# 42mm_Erweiterungsplatine.net
KiCad netlist of a schematic drawn in EAGLE
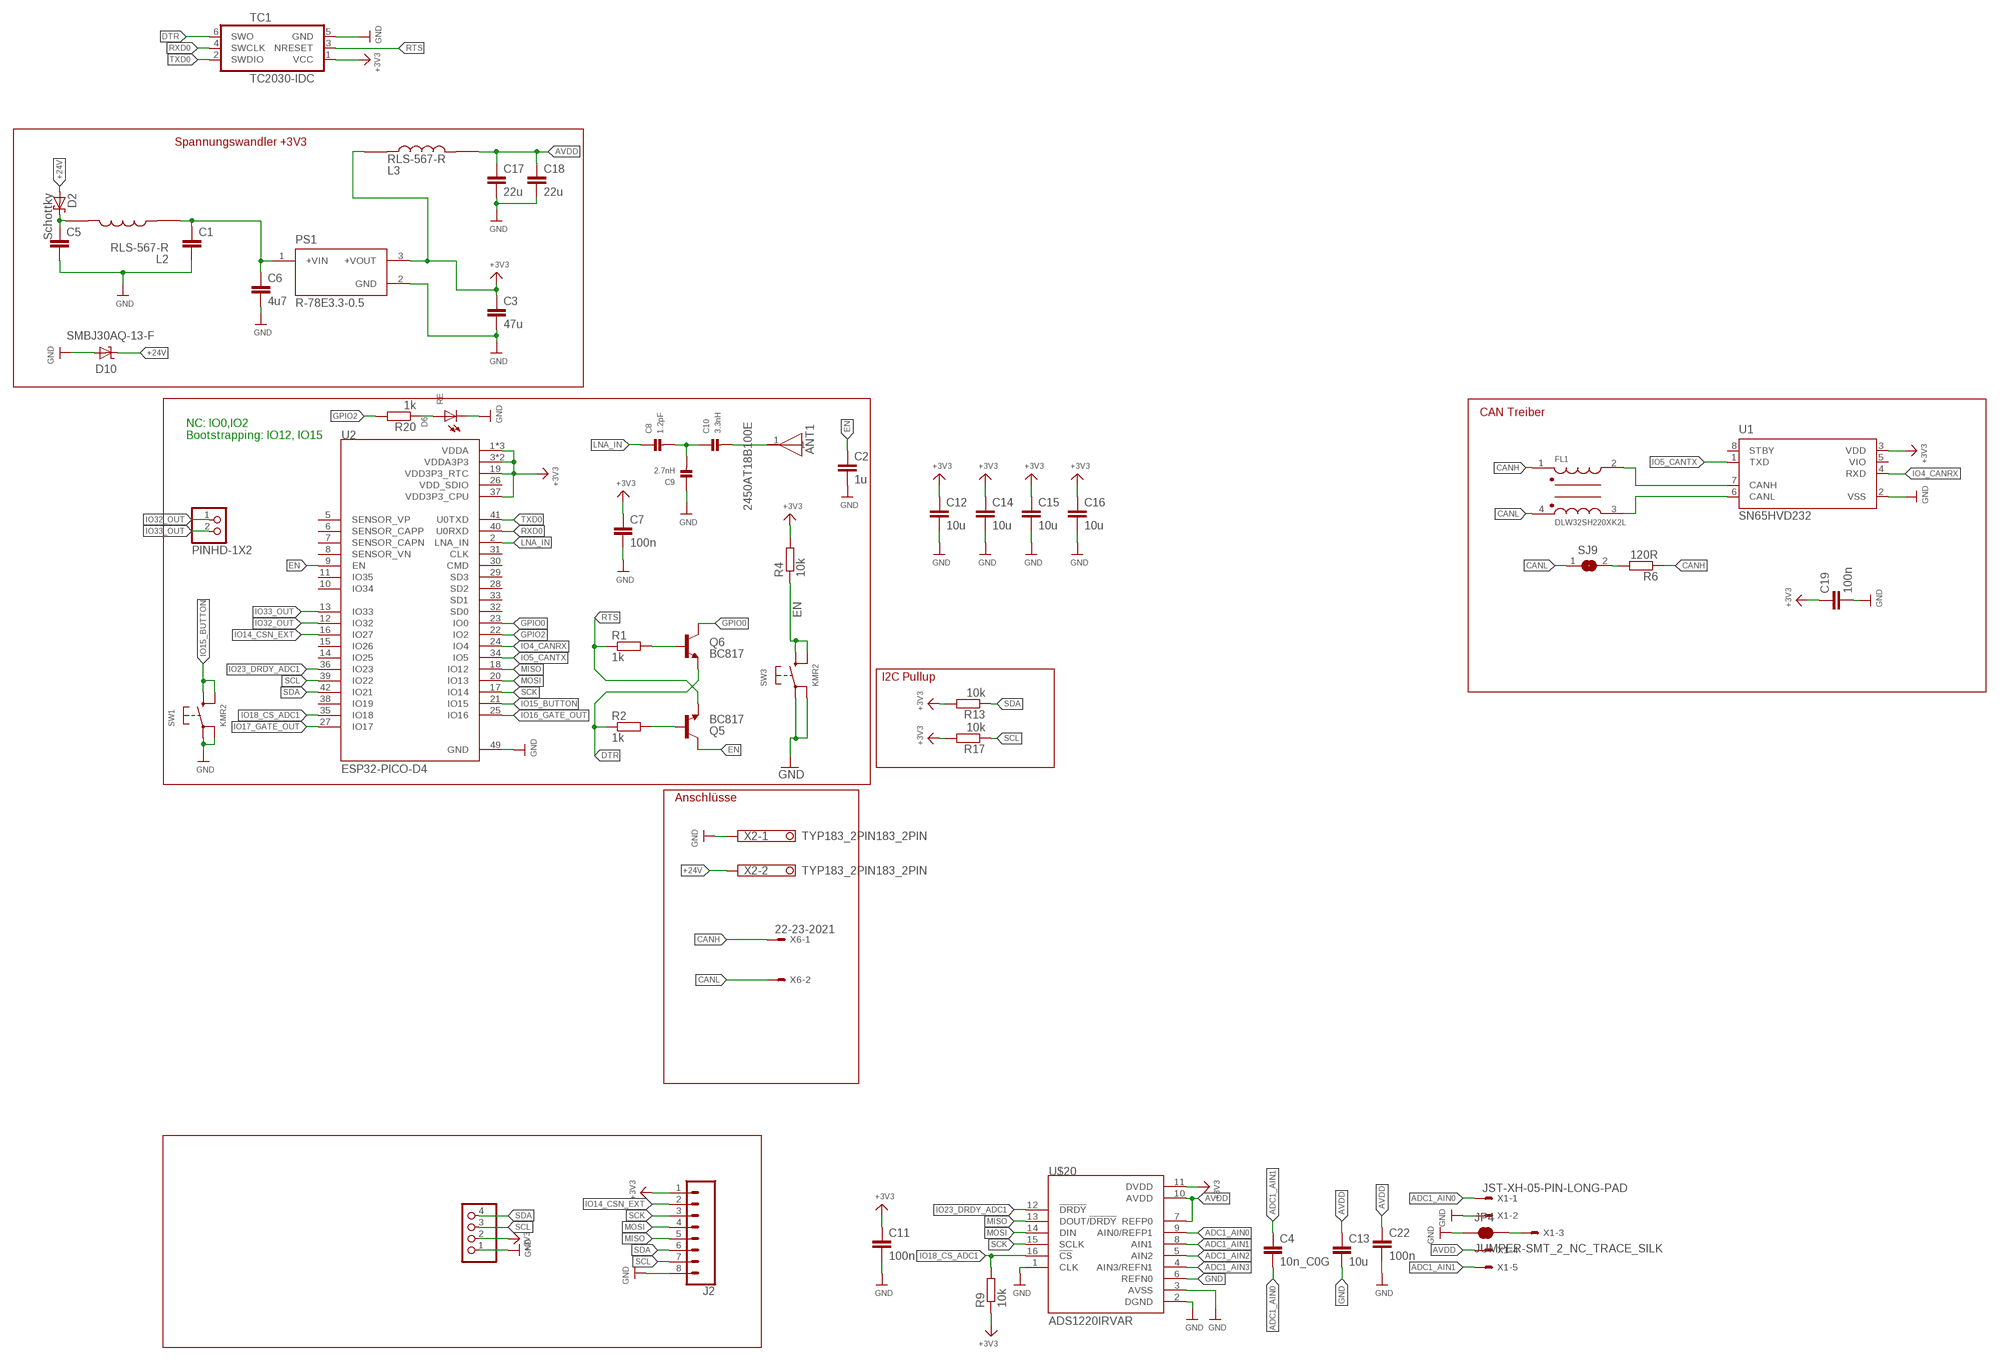
[diagram p0: schematic, sheet 1]

(export (version "E")
  (design (tool "Eeschema 10.0.6"))
  (components
    (comp (ref "ANT1")
      (value "2450AT18B100E")
      (footprint "eagle-import:ANT_2450AT18B100E")
      (fields (field (name "MF") "Johanson Technology"))
      (libsource (lib "eagle-import") (part "2450AT18B100E"))
    )
    (comp (ref "C1")
      (value "C-EUC1206K")
      (footprint "eagle-import:C1206K")
      (libsource (lib "eagle-import") (part "C-EUC1206K"))
    )
    (comp (ref "C2")
      (value "1u")
      (footprint "eagle-import:C0805")
      (libsource (lib "eagle-import") (part "C-EUC0805"))
    )
    (comp (ref "C3")
      (value "47u")
      (footprint "eagle-import:C0805")
      (libsource (lib "eagle-import") (part "C-EUC0805"))
    )
    (comp (ref "C4")
      (value "10n_C0G")
      (footprint "eagle-import:C0805")
      (libsource (lib "eagle-import") (part "C-EUC0805"))
    )
    (comp (ref "C5")
      (value "C-EUC1206K")
      (footprint "eagle-import:C1206K")
      (libsource (lib "eagle-import") (part "C-EUC1206K"))
    )
    (comp (ref "C6")
      (value "4u7")
      (footprint "eagle-import:C0805")
      (libsource (lib "eagle-import") (part "C-EUC0805"))
    )
    (comp (ref "C7")
      (value "100n")
      (footprint "eagle-import:C0805")
      (libsource (lib "eagle-import") (part "C-EUC0805"))
    )
    (comp (ref "C8")
      (value "1.2pF")
      (footprint "eagle-import:_0402MP")
      (libsource (lib "eagle-import") (part "CAP_CERAMIC_0402MP"))
    )
    (comp (ref "C9")
      (value "2.7nH")
      (footprint "eagle-import:_0402MP")
      (libsource (lib "eagle-import") (part "CAP_CERAMIC_0402MP"))
    )
    (comp (ref "C10")
      (value "3.3nH")
      (footprint "eagle-import:_0402MP")
      (libsource (lib "eagle-import") (part "CAP_CERAMIC_0402MP"))
    )
    (comp (ref "C11")
      (value "100n")
      (footprint "eagle-import:C0805")
      (libsource (lib "eagle-import") (part "C-EUC0805"))
    )
    (comp (ref "C12")
      (value "10u")
      (footprint "eagle-import:C0805")
      (libsource (lib "eagle-import") (part "C-EUC0805"))
    )
    (comp (ref "C13")
      (value "10u")
      (footprint "eagle-import:C0805")
      (libsource (lib "eagle-import") (part "C-EUC0805"))
    )
    (comp (ref "C14")
      (value "10u")
      (footprint "eagle-import:C0805")
      (libsource (lib "eagle-import") (part "C-EUC0805"))
    )
    (comp (ref "C15")
      (value "10u")
      (footprint "eagle-import:C0805")
      (libsource (lib "eagle-import") (part "C-EUC0805"))
    )
    (comp (ref "C16")
      (value "10u")
      (footprint "eagle-import:C0805")
      (libsource (lib "eagle-import") (part "C-EUC0805"))
    )
    (comp (ref "C17")
      (value "22u")
      (footprint "eagle-import:C0805")
      (libsource (lib "eagle-import") (part "C-EUC0805"))
    )
    (comp (ref "C18")
      (value "22u")
      (footprint "eagle-import:C0805")
      (libsource (lib "eagle-import") (part "C-EUC0805"))
    )
    (comp (ref "C19")
      (value "100n")
      (footprint "eagle-import:C0805")
      (libsource (lib "eagle-import") (part "C-EUC0805"))
    )
    (comp (ref "C22")
      (value "100n")
      (footprint "eagle-import:C0805")
      (libsource (lib "eagle-import") (part "C-EUC0805"))
    )
    (comp (ref "D2")
      (value "Schottky")
      (footprint "eagle-import:SMB")
      (libsource (lib "eagle-import") (part "SCHOTTKY-DIODESMD"))
    )
    (comp (ref "D6")
      (value "RE")
      (footprint "eagle-import:CHIP-LED0805")
      (libsource (lib "eagle-import") (part "LEDCHIP-LED0805"))
    )
    (comp (ref "D10")
      (value "SMBJ30AQ-13-F")
      (footprint "eagle-import:SMBJ")
      (libsource (lib "eagle-import") (part "SUPPRESSOR-SMBJ"))
    )
    (comp (ref "FL1")
      (value "DLW32SH220XK2L")
      (footprint "eagle-import:FIL_DLW32SH110XK2L")
      (fields (field (name "MF") "Murata") (field (name "MP") "DLW32SH110XK2L"))
      (libsource (lib "eagle-import") (part "DLW32SH110XK2L"))
    )
    (comp (ref "J2")
      (value "CONN_08BM08B-SRSS-TB")
      (footprint "eagle-import:BM08B-SRSS-TB")
      (libsource (lib "eagle-import") (part "CONN_08BM08B-SRSS-TB"))
    )
    (comp (ref "JP1")
      (value "PINHD-1X4")
      (footprint "eagle-import:1X04")
      (libsource (lib "eagle-import") (part "PINHD-1X4"))
    )
    (comp (ref "JP4")
      (value "JUMPER-SMT_2_NC_TRACE_SILK")
      (footprint "eagle-import:SMT-JUMPER_2_NC_TRACE_SILK")
      (libsource (lib "eagle-import") (part "JUMPER-SMT_2_NC_TRACE_SILK"))
    )
    (comp (ref "JP5")
      (value "PINHD-1X2")
      (footprint "eagle-import:1X02")
      (libsource (lib "eagle-import") (part "PINHD-1X2"))
    )
    (comp (ref "L2")
      (value "RLS-567-R")
      (footprint "eagle-import:IND_RLS-567-R")
      (fields (field (name "MF") "Recom Power"))
      (libsource (lib "eagle-import") (part "RLS-567-R"))
    )
    (comp (ref "L3")
      (value "RLS-567-R")
      (footprint "eagle-import:IND_RLS-567-R")
      (fields (field (name "MF") "Recom Power"))
      (libsource (lib "eagle-import") (part "RLS-567-R"))
    )
    (comp (ref "PS1")
      (value "R-78E3.3-0.5")
      (footprint "eagle-import:CONV_R-78E3.3-0.5")
      (fields (field (name "MF") "Recom Power"))
      (libsource (lib "eagle-import") (part "R-78E3.3-0.5"))
    )
    (comp (ref "Q5")
      (value "BC817")
      (footprint "eagle-import:SOT23-3")
      (libsource (lib "eagle-import") (part "TRANSISTOR_NPNSOT23-3"))
    )
    (comp (ref "Q6")
      (value "BC817")
      (footprint "eagle-import:SOT23-3")
      (libsource (lib "eagle-import") (part "TRANSISTOR_NPNSOT23-3"))
    )
    (comp (ref "R1")
      (value "1k")
      (footprint "eagle-import:R0805")
      (libsource (lib "eagle-import") (part "R-EU_R0805"))
    )
    (comp (ref "R2")
      (value "1k")
      (footprint "eagle-import:R0805")
      (libsource (lib "eagle-import") (part "R-EU_R0805"))
    )
    (comp (ref "R4")
      (value "10k")
      (footprint "eagle-import:R0805")
      (libsource (lib "eagle-import") (part "R-EU_R0805"))
    )
    (comp (ref "R6")
      (value "120R")
      (footprint "eagle-import:R0805")
      (libsource (lib "eagle-import") (part "R-EU_R0805"))
    )
    (comp (ref "R9")
      (value "10k")
      (footprint "eagle-import:R0805")
      (libsource (lib "eagle-import") (part "R-EU_R0805"))
    )
    (comp (ref "R13")
      (value "10k")
      (footprint "eagle-import:R0805")
      (libsource (lib "eagle-import") (part "R-EU_R0805"))
    )
    (comp (ref "R17")
      (value "10k")
      (footprint "eagle-import:R0805")
      (libsource (lib "eagle-import") (part "R-EU_R0805"))
    )
    (comp (ref "R20")
      (value "1k")
      (footprint "eagle-import:R0805")
      (libsource (lib "eagle-import") (part "R-EU_R0805"))
    )
    (comp (ref "SJ9") (value "SJ") (footprint "eagle-import:SJ") (libsource (lib "eagle-import") (part "SJ")))
    (comp (ref "SW1")
      (value "KMR2")
      (footprint "eagle-import:BTN_KMR2_4.6X2.8")
      (libsource (lib "eagle-import") (part "SWITCH_TACT_SMT4.6X2.8"))
    )
    (comp (ref "SW3")
      (value "KMR2")
      (footprint "eagle-import:BTN_KMR2_4.6X2.8")
      (libsource (lib "eagle-import") (part "SWITCH_TACT_SMT4.6X2.8"))
    )
    (comp (ref "TC1")
      (value "TC2030-IDC")
      (footprint "eagle-import:TC2030-IDC")
      (fields (field (name "MF") "Tag-Connect LLC"))
      (libsource (lib "eagle-import") (part "TC2030-IDC"))
    )
    (comp (ref "U$20")
      (value "ADS1220IRVAR")
      (footprint "eagle-import:QFN50P350X350X100-17N214X214")
      (libsource (lib "eagle-import") (part "ADS1220IRVAR"))
    )
    (comp (ref "U1")
      (value "SN65HVD232")
      (footprint "eagle-import:SOIC127P600X175-8N")
      (fields (field (name "MF") "Microchip") (field (name "MP") "MCP2562-E/SN"))
      (libsource (lib "eagle-import") (part "MCP2562-E/SN"))
    )
    (comp (ref "U2")
      (value "ESP32-PICO-D4")
      (footprint "eagle-import:PQFN50P700X700X104-49N")
      (fields (field (name "MF") "Espressif Systems"))
      (libsource (lib "eagle-import") (part "ESP32-PICO-D4"))
    )
    (comp (ref "X1")
      (value "JST-XH-05-PIN-LONG-PAD")
      (footprint "eagle-import:JST-XH-05-PACKAGE-LONG-PAD")
      (libsource (lib "eagle-import") (part "JST-XH-05-PIN-LONG-PAD"))
    )
    (comp (ref "X2")
      (value "TYP183_2PIN183_2PIN")
      (footprint "eagle-import:TYP183_FT_2PIN")
      (libsource (lib "eagle-import") (part "TYP183_2PIN183_2PIN"))
    )
    (comp (ref "X6")
      (value "22-23-2021")
      (footprint "eagle-import:22-23-2021")
      (fields (field (name "MF") "MOLEX"))
      (libsource (lib "eagle-import") (part "22-23-2021"))
    )
  )
  (nets
    (net (code "1") (name "+3V3") (class "Default")
      (node (ref "C11") (pin "1") (pinfunction "1_1") (pintype "passive"))
      (node (ref "C12") (pin "1") (pinfunction "1_1") (pintype "passive"))
      (node (ref "C14") (pin "1") (pinfunction "1_1") (pintype "passive"))
      (node (ref "C15") (pin "1") (pinfunction "1_1") (pintype "passive"))
      (node (ref "C16") (pin "1") (pinfunction "1_1") (pintype "passive"))
      (node (ref "C19") (pin "1") (pinfunction "1_1") (pintype "passive"))
      (node (ref "C3") (pin "1") (pinfunction "1_1") (pintype "passive"))
      (node (ref "C7") (pin "1") (pinfunction "1_1") (pintype "passive"))
      (node (ref "J2") (pin "1") (pinfunction "1_1") (pintype "passive"))
      (node (ref "JP1") (pin "2") (pinfunction "2_2") (pintype "passive"))
      (node (ref "L3") (pin "1") (pinfunction "1_1") (pintype "passive"))
      (node (ref "PS1") (pin "3") (pinfunction "+VOUT_3") (pintype "output"))
      (node (ref "R13") (pin "2") (pinfunction "2_2") (pintype "passive"))
      (node (ref "R17") (pin "2") (pinfunction "2_2") (pintype "passive"))
      (node (ref "R4") (pin "2") (pinfunction "2_2") (pintype "passive"))
      (node (ref "R9") (pin "1") (pinfunction "1_1") (pintype "passive"))
      (node (ref "TC1") (pin "1") (pinfunction "VCC_1") (pintype "passive"))
      (node (ref "U$20") (pin "11") (pinfunction "DVDD_11") (pintype "bidirectional"))
      (node (ref "U1") (pin "3") (pinfunction "VDD_3") (pintype "power_in"))
      (node (ref "U2") (pin "1") (pinfunction "VDDA_1") (pintype "power_in"))
      (node (ref "U2") (pin "19") (pinfunction "VDD3P3_RTC_19") (pintype "power_in"))
      (node (ref "U2") (pin "3") (pinfunction "VDDA3P3_3") (pintype "power_in"))
      (node (ref "U2") (pin "37") (pinfunction "VDD3P3_CPU_37") (pintype "power_in"))
      (node (ref "U2") (pin "4") (pinfunction "VDDA3P3_4") (pintype "power_in"))
      (node (ref "U2") (pin "43") (pinfunction "VDDA_43") (pintype "power_in"))
      (node (ref "U2") (pin "46") (pinfunction "VDDA_46") (pintype "power_in"))
    )
    (net (code "2") (name "+24V") (class "Default")
      (node (ref "D10") (pin "C") (pinfunction "C_C") (pintype "passive"))
      (node (ref "D2") (pin "A") (pinfunction "A_A") (pintype "passive"))
      (node (ref "X2") (pin "2") (pinfunction "K_2") (pintype "passive"))
    )
    (net (code "3") (name "/VDD_SDIO") (class "Default")
      (node (ref "U2") (pin "26") (pinfunction "VDD_SDIO_26") (pintype "power_in"))
    )
    (net (code "4") (name "/VIO") (class "Default")
      (node (ref "U1") (pin "5") (pinfunction "VIO_5") (pintype "power_in"))
    )
    (net (code "5") (name "ADC1_AIN0") (class "Default")
      (node (ref "C4") (pin "2") (pinfunction "2_2") (pintype "passive"))
      (node (ref "U$20") (pin "9") (pinfunction "AIN0/REFP1_9") (pintype "bidirectional"))
      (node (ref "X1") (pin "1") (pinfunction "S_1") (pintype "passive"))
    )
    (net (code "6") (name "ADC1_AIN1") (class "Default")
      (node (ref "C4") (pin "1") (pinfunction "1_1") (pintype "passive"))
      (node (ref "U$20") (pin "8") (pinfunction "AIN1_8") (pintype "bidirectional"))
      (node (ref "X1") (pin "5") (pinfunction "S_5") (pintype "passive"))
    )
    (net (code "7") (name "ADC1_AIN2") (class "Default")
      (node (ref "U$20") (pin "5") (pinfunction "AIN2_5") (pintype "bidirectional"))
    )
    (net (code "8") (name "ADC1_AIN3") (class "Default")
      (node (ref "U$20") (pin "4") (pinfunction "AIN3/REFN1_4") (pintype "bidirectional"))
    )
    (net (code "9") (name "AVDD") (class "Default")
      (node (ref "C13") (pin "1") (pinfunction "1_1") (pintype "passive"))
      (node (ref "C17") (pin "1") (pinfunction "1_1") (pintype "passive"))
      (node (ref "C18") (pin "1") (pinfunction "1_1") (pintype "passive"))
      (node (ref "C22") (pin "1") (pinfunction "1_1") (pintype "passive"))
      (node (ref "L3") (pin "2") (pinfunction "2_2") (pintype "passive"))
      (node (ref "U$20") (pin "10") (pinfunction "AVDD_10") (pintype "bidirectional"))
      (node (ref "U$20") (pin "7") (pinfunction "REFP0_7") (pintype "bidirectional"))
      (node (ref "X1") (pin "4") (pinfunction "S_4") (pintype "passive"))
    )
    (net (code "10") (name "CANH") (class "Default")
      (node (ref "FL1") (pin "1") (pinfunction "1_1") (pintype "passive"))
      (node (ref "R6") (pin "1") (pinfunction "1_1") (pintype "passive"))
      (node (ref "X6") (pin "1") (pinfunction "S_1") (pintype "passive"))
    )
    (net (code "11") (name "CANL") (class "Default")
      (node (ref "FL1") (pin "4") (pinfunction "4_4") (pintype "passive"))
      (node (ref "SJ9") (pin "1") (pinfunction "1_1") (pintype "passive"))
      (node (ref "X6") (pin "2") (pinfunction "S_2") (pintype "passive"))
    )
    (net (code "12") (name "DTR") (class "Default")
      (node (ref "Q6") (pin "2") (pinfunction "E_2") (pintype "passive"))
      (node (ref "R2") (pin "1") (pinfunction "1_1") (pintype "passive"))
      (node (ref "TC1") (pin "6") (pinfunction "SWO_6") (pintype "passive"))
    )
    (net (code "13") (name "EN") (class "Default")
      (node (ref "C2") (pin "1") (pinfunction "1_1") (pintype "passive"))
      (node (ref "Q5") (pin "3") (pinfunction "C_3") (pintype "passive"))
      (node (ref "R4") (pin "1") (pinfunction "1_1") (pintype "passive"))
      (node (ref "SW3") (pin "B") (pinfunction "S_B") (pintype "passive"))
      (node (ref "SW3") (pin "B'") (pinfunction "S1_B'") (pintype "passive"))
      (node (ref "U2") (pin "9") (pinfunction "EN_9") (pintype "input"))
    )
    (net (code "14") (name "GND") (class "Default")
      (node (ref "C1") (pin "2") (pinfunction "2_2") (pintype "passive"))
      (node (ref "C11") (pin "2") (pinfunction "2_2") (pintype "passive"))
      (node (ref "C12") (pin "2") (pinfunction "2_2") (pintype "passive"))
      (node (ref "C13") (pin "2") (pinfunction "2_2") (pintype "passive"))
      (node (ref "C14") (pin "2") (pinfunction "2_2") (pintype "passive"))
      (node (ref "C15") (pin "2") (pinfunction "2_2") (pintype "passive"))
      (node (ref "C16") (pin "2") (pinfunction "2_2") (pintype "passive"))
      (node (ref "C17") (pin "2") (pinfunction "2_2") (pintype "passive"))
      (node (ref "C18") (pin "2") (pinfunction "2_2") (pintype "passive"))
      (node (ref "C19") (pin "2") (pinfunction "2_2") (pintype "passive"))
      (node (ref "C2") (pin "2") (pinfunction "2_2") (pintype "passive"))
      (node (ref "C22") (pin "2") (pinfunction "2_2") (pintype "passive"))
      (node (ref "C3") (pin "2") (pinfunction "2_2") (pintype "passive"))
      (node (ref "C5") (pin "2") (pinfunction "2_2") (pintype "passive"))
      (node (ref "C6") (pin "2") (pinfunction "2_2") (pintype "passive"))
      (node (ref "C7") (pin "2") (pinfunction "2_2") (pintype "passive"))
      (node (ref "C9") (pin "1") (pinfunction "P$1_1") (pintype "passive"))
      (node (ref "D10") (pin "A") (pinfunction "A_A") (pintype "passive"))
      (node (ref "D6") (pin "C") (pinfunction "C_C") (pintype "passive"))
      (node (ref "J2") (pin "8") (pinfunction "8_8") (pintype "passive"))
      (node (ref "JP1") (pin "1") (pinfunction "1_1") (pintype "passive"))
      (node (ref "JP4") (pin "1") (pinfunction "1_1") (pintype "passive"))
      (node (ref "PS1") (pin "2") (pinfunction "GND_2") (pintype "power_in"))
      (node (ref "SW1") (pin "A") (pinfunction "P_A") (pintype "passive"))
      (node (ref "SW1") (pin "A'") (pinfunction "P1_A'") (pintype "passive"))
      (node (ref "SW3") (pin "A") (pinfunction "P_A") (pintype "passive"))
      (node (ref "SW3") (pin "A'") (pinfunction "P1_A'") (pintype "passive"))
      (node (ref "TC1") (pin "5") (pinfunction "GND_5") (pintype "passive"))
      (node (ref "U$20") (pin "1") (pinfunction "CLK_1") (pintype "bidirectional"))
      (node (ref "U$20") (pin "2") (pinfunction "DGND_2") (pintype "bidirectional"))
      (node (ref "U$20") (pin "3") (pinfunction "AVSS_3") (pintype "bidirectional"))
      (node (ref "U$20") (pin "6") (pinfunction "REFN0_6") (pintype "bidirectional"))
      (node (ref "U1") (pin "2") (pinfunction "VSS_2") (pintype "power_in"))
      (node (ref "U2") (pin "49") (pinfunction "GND_49") (pintype "power_in"))
      (node (ref "X1") (pin "2") (pinfunction "S_2") (pintype "passive"))
      (node (ref "X2") (pin "1") (pinfunction "K_1") (pintype "passive"))
    )
    (net (code "15") (name "GPIO0") (class "Default")
      (node (ref "Q6") (pin "3") (pinfunction "C_3") (pintype "passive"))
      (node (ref "U2") (pin "23") (pinfunction "IO0_23") (pintype "bidirectional"))
    )
    (net (code "16") (name "GPIO2") (class "Default")
      (node (ref "R20") (pin "2") (pinfunction "2_2") (pintype "passive"))
      (node (ref "U2") (pin "22") (pinfunction "IO2_22") (pintype "bidirectional"))
    )
    (net (code "17") (name "IO4_CANRX") (class "Default")
      (node (ref "U1") (pin "4") (pinfunction "RXD_4") (pintype "output"))
      (node (ref "U2") (pin "24") (pinfunction "IO4_24") (pintype "bidirectional"))
    )
    (net (code "18") (name "IO5_CANTX") (class "Default")
      (node (ref "U1") (pin "1") (pinfunction "TXD_1") (pintype "input"))
      (node (ref "U2") (pin "34") (pinfunction "IO5_34") (pintype "bidirectional"))
    )
    (net (code "19") (name "IO14_CSN_EXT") (class "Default")
      (node (ref "J2") (pin "2") (pinfunction "2_2") (pintype "passive"))
      (node (ref "U2") (pin "16") (pinfunction "IO27_16") (pintype "bidirectional"))
    )
    (net (code "20") (name "IO15_BUTTON") (class "Default")
      (node (ref "SW1") (pin "B") (pinfunction "S_B") (pintype "passive"))
      (node (ref "SW1") (pin "B'") (pinfunction "S1_B'") (pintype "passive"))
      (node (ref "U2") (pin "21") (pinfunction "IO15_21") (pintype "bidirectional"))
    )
    (net (code "21") (name "IO16_GATE_OUT") (class "Default")
      (node (ref "U2") (pin "25") (pinfunction "IO16_25") (pintype "bidirectional"))
    )
    (net (code "22") (name "IO17_GATE_OUT") (class "Default")
      (node (ref "U2") (pin "27") (pinfunction "IO17_27") (pintype "bidirectional"))
    )
    (net (code "23") (name "IO18_CS_ADC1") (class "Default")
      (node (ref "R9") (pin "2") (pinfunction "2_2") (pintype "passive"))
      (node (ref "U$20") (pin "16") (pinfunction "~{CS}_16") (pintype "bidirectional"))
      (node (ref "U2") (pin "35") (pinfunction "IO18_35") (pintype "bidirectional"))
    )
    (net (code "24") (name "IO23_DRDY_ADC1") (class "Default")
      (node (ref "U$20") (pin "12") (pinfunction "~{DRDY}_12") (pintype "bidirectional"))
      (node (ref "U2") (pin "36") (pinfunction "IO23_36") (pintype "bidirectional"))
    )
    (net (code "25") (name "IO32_OUT") (class "Default")
      (node (ref "JP5") (pin "1") (pinfunction "1_1") (pintype "passive"))
      (node (ref "U2") (pin "12") (pinfunction "IO32_12") (pintype "bidirectional"))
    )
    (net (code "26") (name "IO33_OUT") (class "Default")
      (node (ref "JP5") (pin "2") (pinfunction "2_2") (pintype "passive"))
      (node (ref "U2") (pin "13") (pinfunction "IO33_13") (pintype "bidirectional"))
    )
    (net (code "27") (name "LNA_IN") (class "Default")
      (node (ref "C8") (pin "1") (pinfunction "P$1_1") (pintype "passive"))
      (node (ref "U2") (pin "2") (pinfunction "LNA_IN_2") (pintype "bidirectional"))
    )
    (net (code "28") (name "MISO") (class "Default")
      (node (ref "J2") (pin "5") (pinfunction "5_5") (pintype "passive"))
      (node (ref "U$20") (pin "13") (pinfunction "DOUT/~{DRDY}_13") (pintype "bidirectional"))
      (node (ref "U2") (pin "18") (pinfunction "IO12_18") (pintype "bidirectional"))
    )
    (net (code "29") (name "MOSI") (class "Default")
      (node (ref "J2") (pin "4") (pinfunction "4_4") (pintype "passive"))
      (node (ref "U$20") (pin "14") (pinfunction "DIN_14") (pintype "bidirectional"))
      (node (ref "U2") (pin "20") (pinfunction "IO13_20") (pintype "bidirectional"))
    )
    (net (code "30") (name "Net-(C5-Pad1)") (class "Default")
      (node (ref "C5") (pin "1") (pinfunction "1_1") (pintype "passive"))
      (node (ref "D2") (pin "C") (pinfunction "C_C") (pintype "passive"))
      (node (ref "L2") (pin "2") (pinfunction "2_2") (pintype "passive"))
    )
    (net (code "31") (name "Net-(C10-P$1)") (class "Default")
      (node (ref "C10") (pin "1") (pinfunction "P$1_1") (pintype "passive"))
      (node (ref "C8") (pin "2") (pinfunction "P$2_2") (pintype "passive"))
      (node (ref "C9") (pin "2") (pinfunction "P$2_2") (pintype "passive"))
    )
    (net (code "32") (name "Net-(C10-P$2)") (class "Default")
      (node (ref "ANT1") (pin "1") (pinfunction "1_1") (pintype "input"))
      (node (ref "C10") (pin "2") (pinfunction "P$2_2") (pintype "passive"))
    )
    (net (code "33") (name "Net-(D6-PadA)") (class "Default")
      (node (ref "D6") (pin "A") (pinfunction "A_A") (pintype "passive"))
      (node (ref "R20") (pin "1") (pinfunction "1_1") (pintype "passive"))
    )
    (net (code "34") (name "Net-(PS1-+VIN)") (class "Default")
      (node (ref "C1") (pin "1") (pinfunction "1_1") (pintype "passive"))
      (node (ref "C6") (pin "1") (pinfunction "1_1") (pintype "passive"))
      (node (ref "L2") (pin "1") (pinfunction "1_1") (pintype "passive"))
      (node (ref "PS1") (pin "1") (pinfunction "+VIN_1") (pintype "input"))
    )
    (net (code "35") (name "Net-(Q5-B)") (class "Default")
      (node (ref "Q5") (pin "1") (pinfunction "B_1") (pintype "passive"))
      (node (ref "R2") (pin "2") (pinfunction "2_2") (pintype "passive"))
    )
    (net (code "36") (name "Net-(Q6-B)") (class "Default")
      (node (ref "Q6") (pin "1") (pinfunction "B_1") (pintype "passive"))
      (node (ref "R1") (pin "2") (pinfunction "2_2") (pintype "passive"))
    )
    (net (code "37") (name "Net-(R6-Pad2)") (class "Default")
      (node (ref "R6") (pin "2") (pinfunction "2_2") (pintype "passive"))
      (node (ref "SJ9") (pin "2") (pinfunction "2_2") (pintype "passive"))
    )
    (net (code "38") (name "Net-(U1-CANH)") (class "Default")
      (node (ref "FL1") (pin "2") (pinfunction "2_2") (pintype "passive"))
      (node (ref "U1") (pin "7") (pinfunction "CANH_7") (pintype "input"))
    )
    (net (code "39") (name "Net-(U1-CANL)") (class "Default")
      (node (ref "FL1") (pin "3") (pinfunction "3_3") (pintype "passive"))
      (node (ref "U1") (pin "6") (pinfunction "CANL_6") (pintype "input"))
    )
    (net (code "40") (name "Net-(X1C-S)") (class "Default")
      (node (ref "JP4") (pin "2") (pinfunction "2_2") (pintype "passive"))
      (node (ref "X1") (pin "3") (pinfunction "S_3") (pintype "passive"))
    )
    (net (code "41") (name "RTS") (class "Default")
      (node (ref "Q5") (pin "2") (pinfunction "E_2") (pintype "passive"))
      (node (ref "R1") (pin "1") (pinfunction "1_1") (pintype "passive"))
      (node (ref "TC1") (pin "3") (pinfunction "NRESET_3") (pintype "passive"))
    )
    (net (code "42") (name "RXD0") (class "Default")
      (node (ref "TC1") (pin "4") (pinfunction "SWCLK_4") (pintype "passive"))
      (node (ref "U2") (pin "40") (pinfunction "U0RXD_40") (pintype "bidirectional"))
    )
    (net (code "43") (name "SCK") (class "Default")
      (node (ref "J2") (pin "3") (pinfunction "3_3") (pintype "passive"))
      (node (ref "U$20") (pin "15") (pinfunction "SCLK_15") (pintype "bidirectional"))
      (node (ref "U2") (pin "17") (pinfunction "IO14_17") (pintype "bidirectional"))
    )
    (net (code "44") (name "SCL") (class "Default")
      (node (ref "J2") (pin "7") (pinfunction "7_7") (pintype "passive"))
      (node (ref "JP1") (pin "3") (pinfunction "3_3") (pintype "passive"))
      (node (ref "R17") (pin "1") (pinfunction "1_1") (pintype "passive"))
      (node (ref "U2") (pin "39") (pinfunction "IO22_39") (pintype "bidirectional"))
    )
    (net (code "45") (name "SDA") (class "Default")
      (node (ref "J2") (pin "6") (pinfunction "6_6") (pintype "passive"))
      (node (ref "JP1") (pin "4") (pinfunction "4_4") (pintype "passive"))
      (node (ref "R13") (pin "1") (pinfunction "1_1") (pintype "passive"))
      (node (ref "U2") (pin "42") (pinfunction "IO21_42") (pintype "bidirectional"))
    )
    (net (code "46") (name "TXD0") (class "Default")
      (node (ref "TC1") (pin "2") (pinfunction "SWDIO_2") (pintype "passive"))
      (node (ref "U2") (pin "41") (pinfunction "U0TXD_41") (pintype "bidirectional"))
    )
    (net (code "47") (name "unconnected-(U1-STBY-Pad8)") (class "Default")
      (node (ref "U1") (pin "8") (pinfunction "STBY_8") (pintype "input"))
    )
    (net (code "48") (name "unconnected-(U2-CLK-Pad31)") (class "Default")
      (node (ref "U2") (pin "31") (pinfunction "CLK_31") (pintype "bidirectional"))
    )
    (net (code "49") (name "unconnected-(U2-CMD-Pad30)") (class "Default")
      (node (ref "U2") (pin "30") (pinfunction "CMD_30") (pintype "bidirectional"))
    )
    (net (code "50") (name "unconnected-(U2-IO19-Pad38)") (class "Default")
      (node (ref "U2") (pin "38") (pinfunction "IO19_38") (pintype "bidirectional"))
    )
    (net (code "51") (name "unconnected-(U2-IO25-Pad14)") (class "Default")
      (node (ref "U2") (pin "14") (pinfunction "IO25_14") (pintype "bidirectional"))
    )
    (net (code "52") (name "unconnected-(U2-IO26-Pad15)") (class "Default")
      (node (ref "U2") (pin "15") (pinfunction "IO26_15") (pintype "bidirectional"))
    )
    (net (code "53") (name "unconnected-(U2-IO34-Pad10)") (class "Default")
      (node (ref "U2") (pin "10") (pinfunction "IO34_10") (pintype "input"))
    )
    (net (code "54") (name "unconnected-(U2-IO35-Pad11)") (class "Default")
      (node (ref "U2") (pin "11") (pinfunction "IO35_11") (pintype "input"))
    )
    (net (code "55") (name "unconnected-(U2-SD0-Pad32)") (class "Default")
      (node (ref "U2") (pin "32") (pinfunction "SD0_32") (pintype "bidirectional"))
    )
    (net (code "56") (name "unconnected-(U2-SD1-Pad33)") (class "Default")
      (node (ref "U2") (pin "33") (pinfunction "SD1_33") (pintype "bidirectional"))
    )
    (net (code "57") (name "unconnected-(U2-SD2-Pad28)") (class "Default")
      (node (ref "U2") (pin "28") (pinfunction "SD2_28") (pintype "bidirectional"))
    )
    (net (code "58") (name "unconnected-(U2-SD3-Pad29)") (class "Default")
      (node (ref "U2") (pin "29") (pinfunction "SD3_29") (pintype "bidirectional"))
    )
    (net (code "59") (name "unconnected-(U2-SENSOR_CAPN-Pad7)") (class "Default")
      (node (ref "U2") (pin "7") (pinfunction "SENSOR_CAPN_7") (pintype "input"))
    )
    (net (code "60") (name "unconnected-(U2-SENSOR_CAPP-Pad6)") (class "Default")
      (node (ref "U2") (pin "6") (pinfunction "SENSOR_CAPP_6") (pintype "input"))
    )
    (net (code "61") (name "unconnected-(U2-SENSOR_VN-Pad8)") (class "Default")
      (node (ref "U2") (pin "8") (pinfunction "SENSOR_VN_8") (pintype "input"))
    )
    (net (code "62") (name "unconnected-(U2-SENSOR_VP-Pad5)") (class "Default")
      (node (ref "U2") (pin "5") (pinfunction "SENSOR_VP_5") (pintype "input"))
    )
  )
)
